# untitled.net
KiCad netlist of a schematic drawn in EAGLE
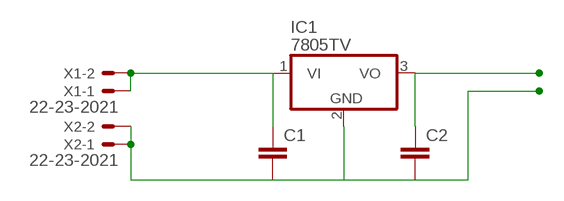
[diagram p0: schematic, sheet 1]

(export (version "E")
  (design (tool "Eeschema 10.0.6"))
  (components
    (comp (ref "C1")
      (value "C-EUC1206")
      (footprint "eagle-import:C1206")
      (libsource (lib "eagle-import") (part "C-EUC1206"))
    )
    (comp (ref "C2")
      (value "C-EUC1206")
      (footprint "eagle-import:C1206")
      (libsource (lib "eagle-import") (part "C-EUC1206"))
    )
    (comp (ref "IC1")
      (value "7805TV")
      (footprint "eagle-import:TO220V")
      (libsource (lib "eagle-import") (part "78TV05"))
    )
    (comp (ref "X1")
      (value "22-23-2021")
      (footprint "eagle-import:22-23-2021")
      (fields (field (name "MF") "MOLEX"))
      (libsource (lib "eagle-import") (part "22-23-2021"))
    )
    (comp (ref "X2")
      (value "22-23-2021")
      (footprint "eagle-import:22-23-2021")
      (fields (field (name "MF") "MOLEX"))
      (libsource (lib "eagle-import") (part "22-23-2021"))
    )
  )
  (nets
    (net (code "1") (name "Net-(IC1-GND)") (class "Default")
      (node (ref "C1") (pin "2") (pinfunction "2_2") (pintype "passive"))
      (node (ref "C2") (pin "2") (pinfunction "2_2") (pintype "passive"))
      (node (ref "IC1") (pin "2") (pinfunction "GND_2") (pintype "passive"))
      (node (ref "X2") (pin "1") (pinfunction "S_1") (pintype "passive"))
      (node (ref "X2") (pin "2") (pinfunction "S_2") (pintype "passive"))
    )
    (net (code "2") (name "Net-(IC1-VI)") (class "Default")
      (node (ref "C1") (pin "1") (pinfunction "1_1") (pintype "passive"))
      (node (ref "IC1") (pin "1") (pinfunction "VI_1") (pintype "input"))
      (node (ref "X1") (pin "1") (pinfunction "S_1") (pintype "passive"))
      (node (ref "X1") (pin "2") (pinfunction "S_2") (pintype "passive"))
    )
    (net (code "3") (name "Net-(IC1-VO)") (class "Default")
      (node (ref "C2") (pin "1") (pinfunction "1_1") (pintype "passive"))
      (node (ref "IC1") (pin "3") (pinfunction "VO_3") (pintype "passive"))
    )
  )
)
